# io-16x-fused-fm_v1_0_0.net
KiCad netlist of a schematic drawn in EAGLE
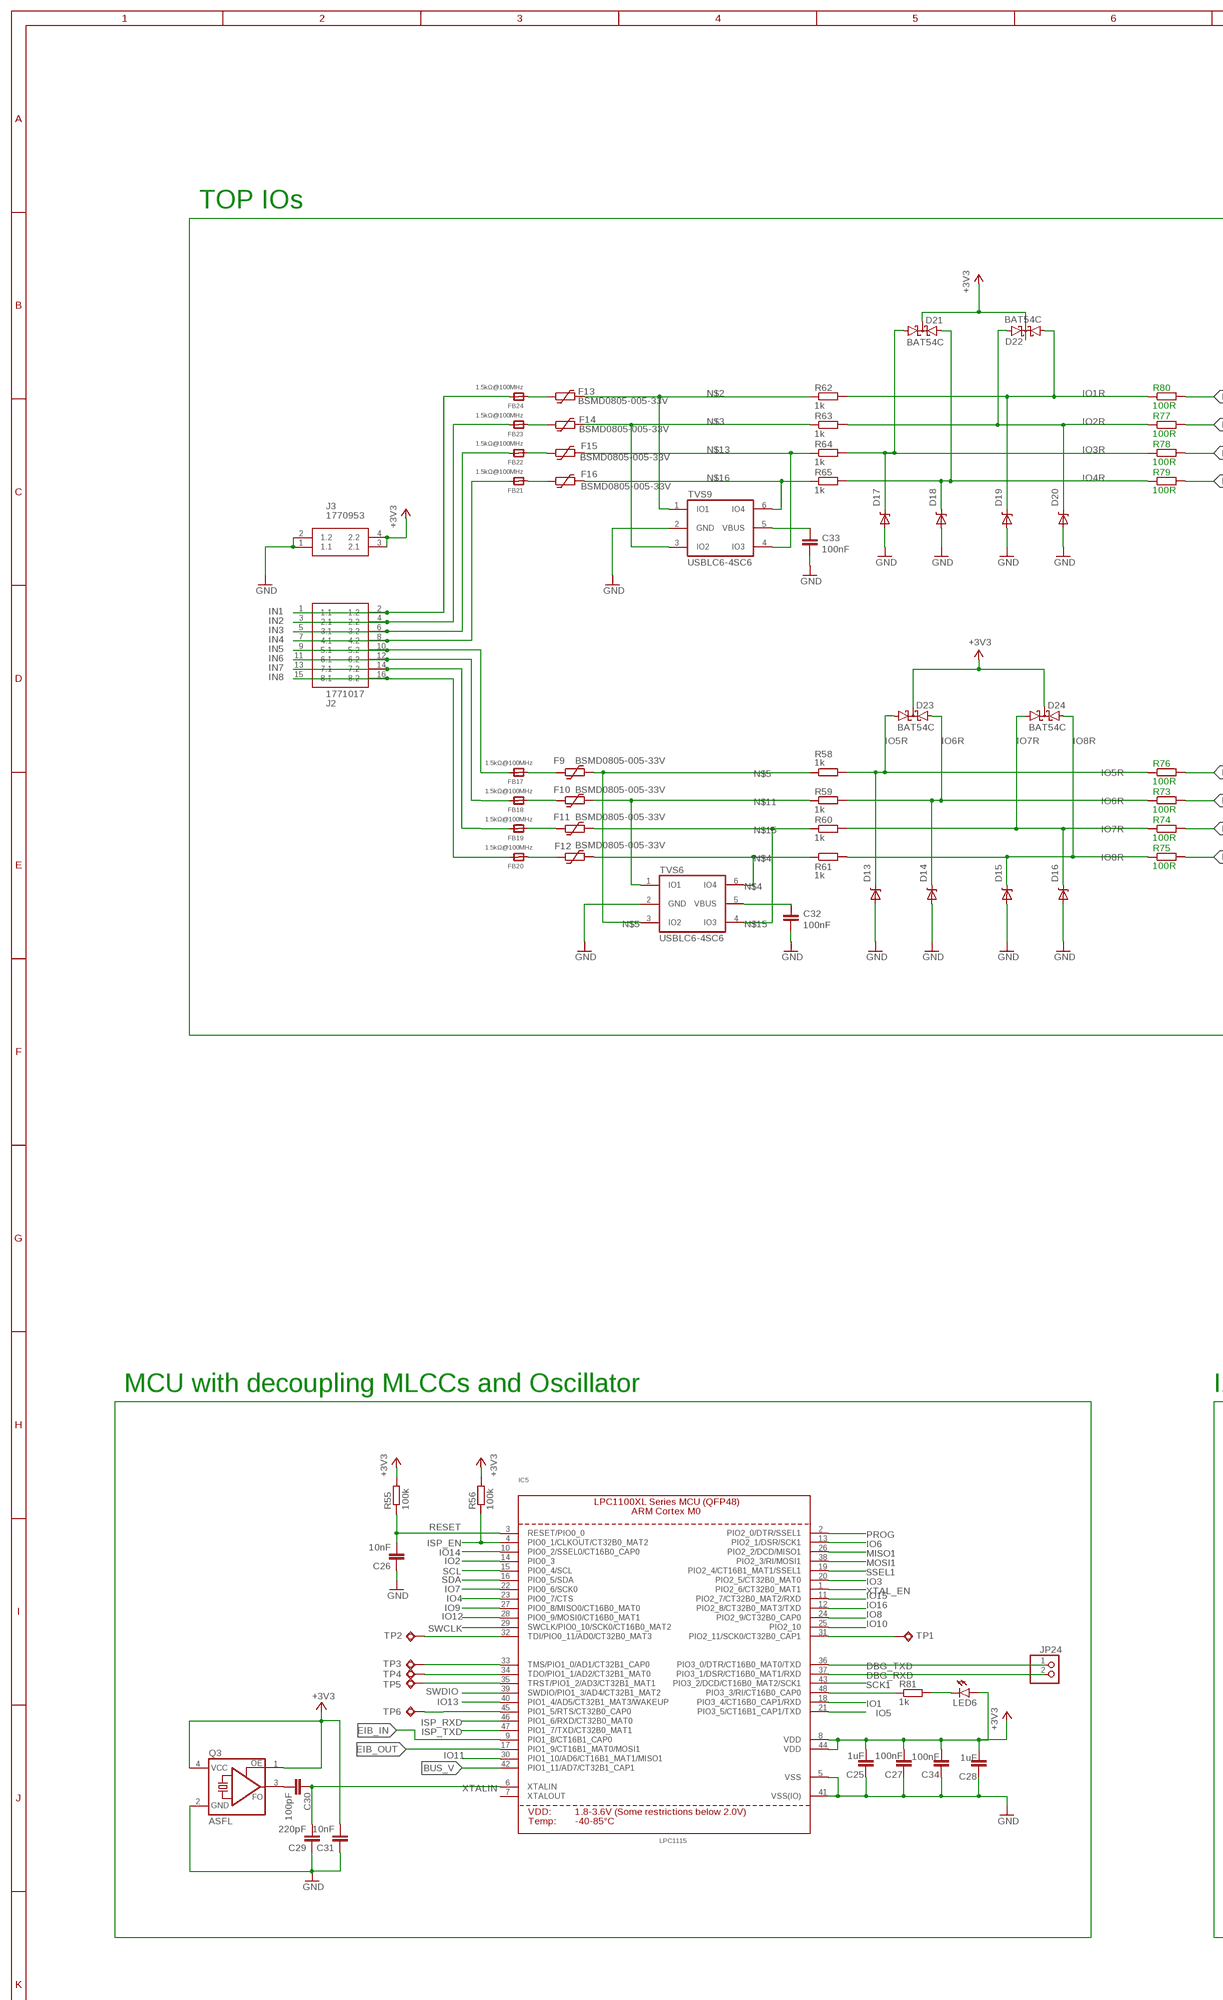
[diagram p0: schematic, sheet 1, part 1 of 3]
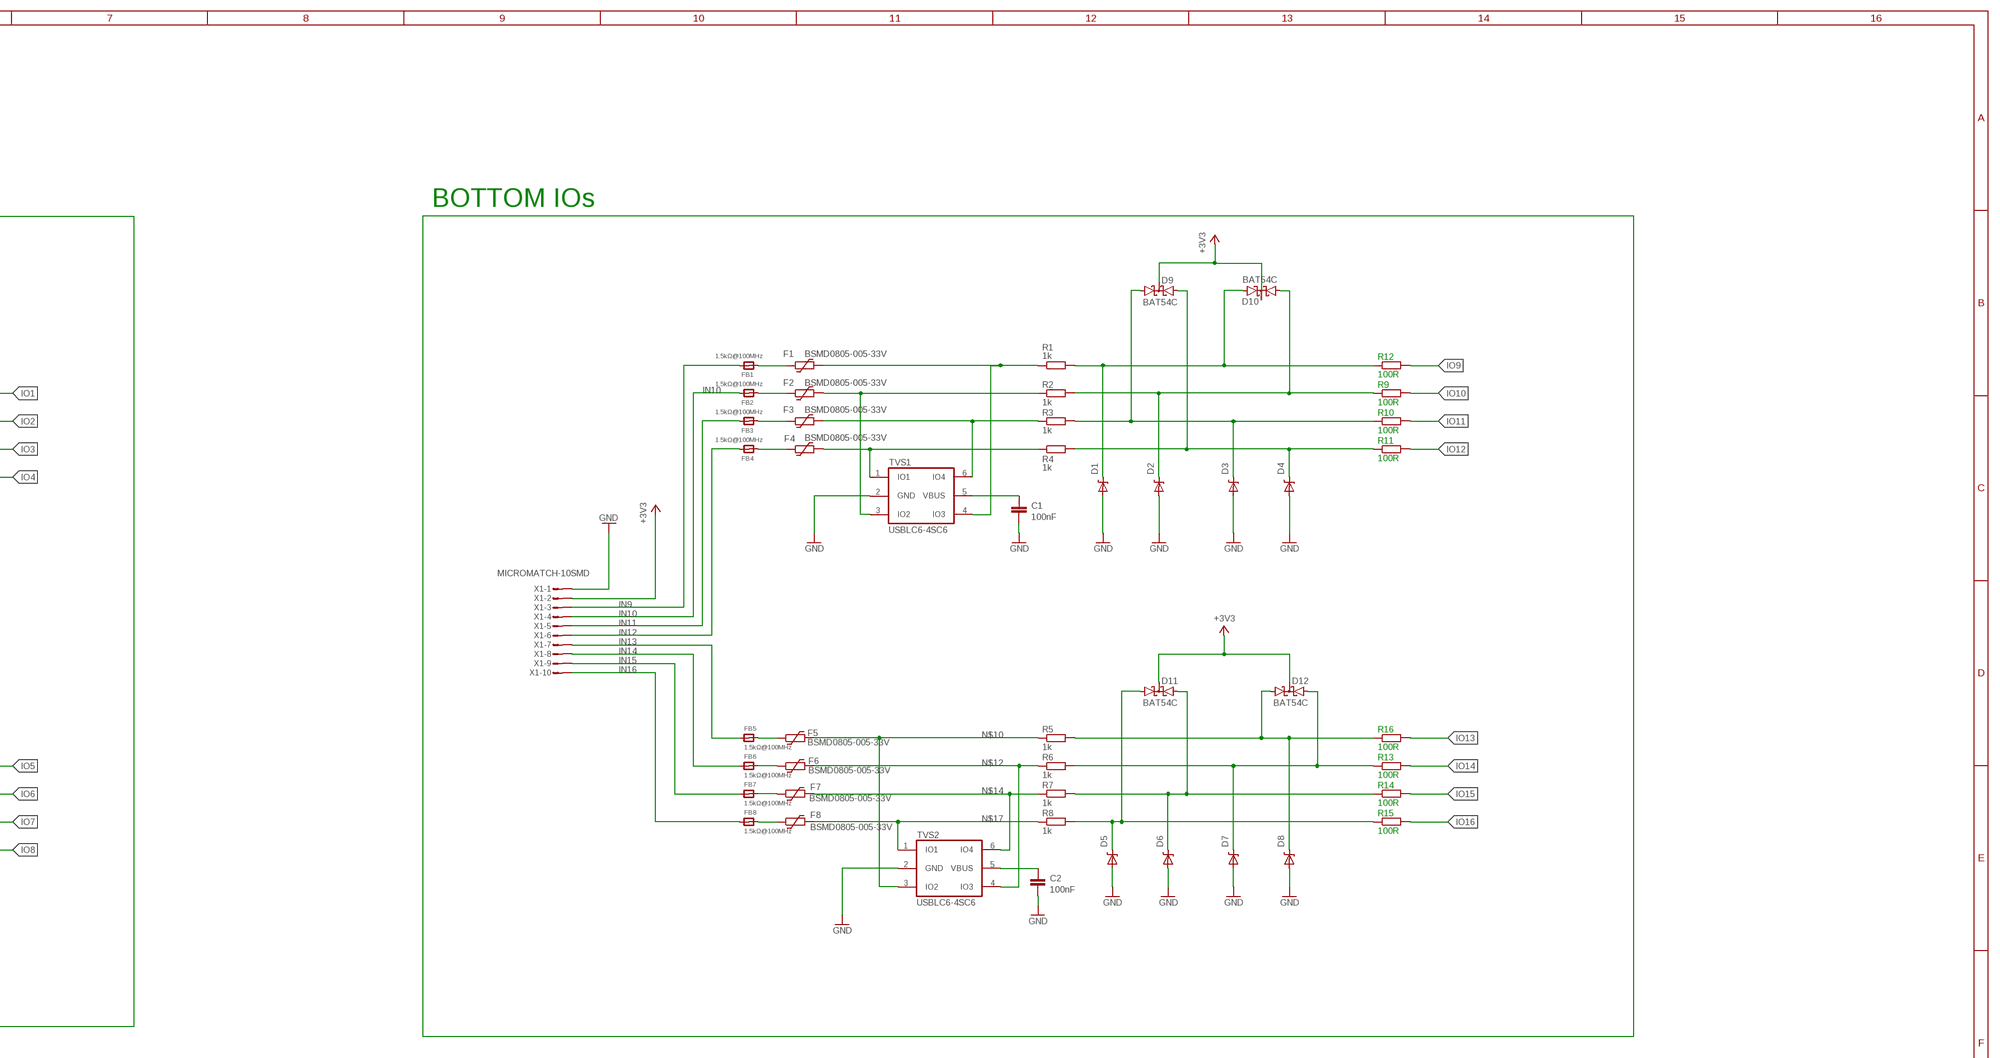
[diagram p1: schematic, sheet 1, part 2 of 3]
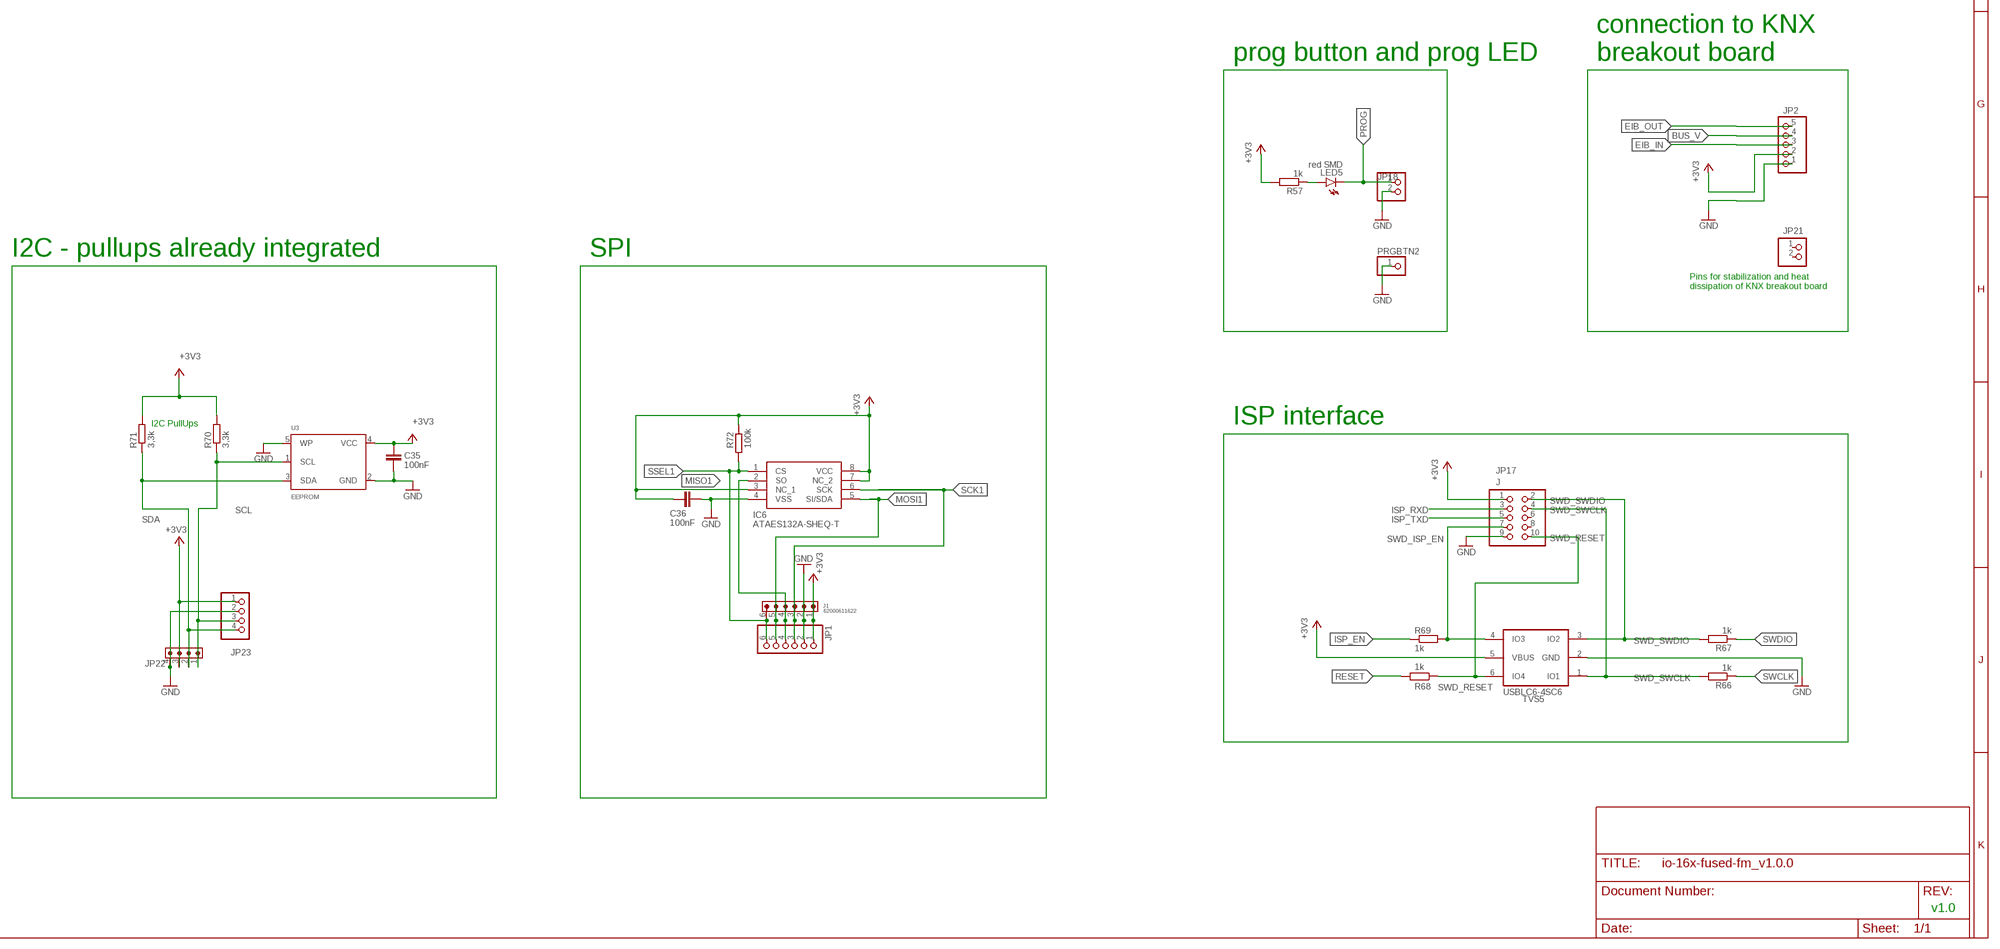
[diagram p2: schematic, sheet 1, part 3 of 3]

(export (version "E")
  (design (tool "Eeschema 10.0.6"))
  (components
    (comp (ref "C1")
      (value "100nF")
      (footprint "eagle-import:C0805")
      (libsource (lib "eagle-import") (part "C-EUC0805"))
    )
    (comp (ref "C2")
      (value "100nF")
      (footprint "eagle-import:C0805")
      (libsource (lib "eagle-import") (part "C-EUC0805"))
    )
    (comp (ref "C25")
      (value "1uF")
      (footprint "eagle-import:C0805")
      (libsource (lib "eagle-import") (part "C-EUC0805"))
    )
    (comp (ref "C26")
      (value "10nF")
      (footprint "eagle-import:C0805")
      (libsource (lib "eagle-import") (part "C-EUC0805"))
    )
    (comp (ref "C27")
      (value "100nF")
      (footprint "eagle-import:C0805")
      (libsource (lib "eagle-import") (part "C-EUC0805"))
    )
    (comp (ref "C28")
      (value "1uF")
      (footprint "eagle-import:C0805")
      (libsource (lib "eagle-import") (part "C-EUC0805"))
    )
    (comp (ref "C29")
      (value "220pF")
      (footprint "eagle-import:C0805")
      (libsource (lib "eagle-import") (part "C-EUC0805"))
    )
    (comp (ref "C30")
      (value "100pF")
      (footprint "eagle-import:C0805")
      (libsource (lib "eagle-import") (part "C-EUC0805"))
    )
    (comp (ref "C31")
      (value "10nF")
      (footprint "eagle-import:C0805")
      (libsource (lib "eagle-import") (part "C-EUC0805"))
    )
    (comp (ref "C32")
      (value "100nF")
      (footprint "eagle-import:C0805")
      (libsource (lib "eagle-import") (part "C-EUC0805"))
    )
    (comp (ref "C33")
      (value "100nF")
      (footprint "eagle-import:C0805")
      (libsource (lib "eagle-import") (part "C-EUC0805"))
    )
    (comp (ref "C34")
      (value "100nF")
      (footprint "eagle-import:C0805")
      (libsource (lib "eagle-import") (part "C-EUC0805"))
    )
    (comp (ref "C35")
      (value "100nF")
      (footprint "eagle-import:C0805")
      (libsource (lib "eagle-import") (part "C-EUC0805"))
    )
    (comp (ref "C36")
      (value "100nF")
      (footprint "eagle-import:C0805")
      (libsource (lib "eagle-import") (part "C-EUC0805"))
    )
    (comp (ref "D1")
      (value "DDZ9684")
      (footprint "eagle-import:SOD-123")
      (libsource (lib "eagle-import") (part "DIODE-ZENERSOD-123"))
    )
    (comp (ref "D2")
      (value "DDZ9684")
      (footprint "eagle-import:SOD-123")
      (libsource (lib "eagle-import") (part "DIODE-ZENERSOD-123"))
    )
    (comp (ref "D3")
      (value "DDZ9684")
      (footprint "eagle-import:SOD-123")
      (libsource (lib "eagle-import") (part "DIODE-ZENERSOD-123"))
    )
    (comp (ref "D4")
      (value "DDZ9684")
      (footprint "eagle-import:SOD-123")
      (libsource (lib "eagle-import") (part "DIODE-ZENERSOD-123"))
    )
    (comp (ref "D5")
      (value "DDZ9684")
      (footprint "eagle-import:SOD-123")
      (libsource (lib "eagle-import") (part "DIODE-ZENERSOD-123"))
    )
    (comp (ref "D6")
      (value "DDZ9684")
      (footprint "eagle-import:SOD-123")
      (libsource (lib "eagle-import") (part "DIODE-ZENERSOD-123"))
    )
    (comp (ref "D7")
      (value "DDZ9684")
      (footprint "eagle-import:SOD-123")
      (libsource (lib "eagle-import") (part "DIODE-ZENERSOD-123"))
    )
    (comp (ref "D8")
      (value "DDZ9684")
      (footprint "eagle-import:SOD-123")
      (libsource (lib "eagle-import") (part "DIODE-ZENERSOD-123"))
    )
    (comp (ref "D9")
      (value "BAT54C")
      (footprint "eagle-import:SOT23")
      (libsource (lib "eagle-import") (part "BAT54C"))
    )
    (comp (ref "D10")
      (value "BAT54C")
      (footprint "eagle-import:SOT23")
      (libsource (lib "eagle-import") (part "BAT54C"))
    )
    (comp (ref "D11")
      (value "BAT54C")
      (footprint "eagle-import:SOT23")
      (libsource (lib "eagle-import") (part "BAT54C"))
    )
    (comp (ref "D12")
      (value "BAT54C")
      (footprint "eagle-import:SOT23")
      (libsource (lib "eagle-import") (part "BAT54C"))
    )
    (comp (ref "D13")
      (value "DDZ9684")
      (footprint "eagle-import:SOD-123")
      (libsource (lib "eagle-import") (part "DIODE-ZENERSOD-123"))
    )
    (comp (ref "D14")
      (value "DDZ9684")
      (footprint "eagle-import:SOD-123")
      (libsource (lib "eagle-import") (part "DIODE-ZENERSOD-123"))
    )
    (comp (ref "D15")
      (value "DDZ9684")
      (footprint "eagle-import:SOD-123")
      (libsource (lib "eagle-import") (part "DIODE-ZENERSOD-123"))
    )
    (comp (ref "D16")
      (value "DDZ9684")
      (footprint "eagle-import:SOD-123")
      (libsource (lib "eagle-import") (part "DIODE-ZENERSOD-123"))
    )
    (comp (ref "D17")
      (value "DDZ9684")
      (footprint "eagle-import:SOD-123")
      (libsource (lib "eagle-import") (part "DIODE-ZENERSOD-123"))
    )
    (comp (ref "D18")
      (value "DDZ9684")
      (footprint "eagle-import:SOD-123")
      (libsource (lib "eagle-import") (part "DIODE-ZENERSOD-123"))
    )
    (comp (ref "D19")
      (value "DDZ9684")
      (footprint "eagle-import:SOD-123")
      (libsource (lib "eagle-import") (part "DIODE-ZENERSOD-123"))
    )
    (comp (ref "D20")
      (value "DDZ9684")
      (footprint "eagle-import:SOD-123")
      (libsource (lib "eagle-import") (part "DIODE-ZENERSOD-123"))
    )
    (comp (ref "D21")
      (value "BAT54C")
      (footprint "eagle-import:SOT23")
      (libsource (lib "eagle-import") (part "BAT54C"))
    )
    (comp (ref "D22")
      (value "BAT54C")
      (footprint "eagle-import:SOT23")
      (libsource (lib "eagle-import") (part "BAT54C"))
    )
    (comp (ref "D23")
      (value "BAT54C")
      (footprint "eagle-import:SOT23")
      (libsource (lib "eagle-import") (part "BAT54C"))
    )
    (comp (ref "D24")
      (value "BAT54C")
      (footprint "eagle-import:SOT23")
      (libsource (lib "eagle-import") (part "BAT54C"))
    )
    (comp (ref "F1")
      (value "BSMD0805-005-33V")
      (footprint "eagle-import:0805L")
      (fields (field (name "MF") "Littelfuse") (field (name "MPN") "0805L035"))
      (libsource (lib "eagle-import") (part "?0805L035"))
    )
    (comp (ref "F2")
      (value "BSMD0805-005-33V")
      (footprint "eagle-import:0805L")
      (fields (field (name "MF") "Littelfuse") (field (name "MPN") "0805L035"))
      (libsource (lib "eagle-import") (part "?0805L035"))
    )
    (comp (ref "F3")
      (value "BSMD0805-005-33V")
      (footprint "eagle-import:0805L")
      (fields (field (name "MF") "Littelfuse") (field (name "MPN") "0805L035"))
      (libsource (lib "eagle-import") (part "?0805L035"))
    )
    (comp (ref "F4")
      (value "BSMD0805-005-33V")
      (footprint "eagle-import:0805L")
      (fields (field (name "MF") "Littelfuse") (field (name "MPN") "0805L035"))
      (libsource (lib "eagle-import") (part "?0805L035"))
    )
    (comp (ref "F5")
      (value "BSMD0805-005-33V")
      (footprint "eagle-import:0805L")
      (fields (field (name "MF") "Littelfuse") (field (name "MPN") "0805L035"))
      (libsource (lib "eagle-import") (part "?0805L035"))
    )
    (comp (ref "F6")
      (value "BSMD0805-005-33V")
      (footprint "eagle-import:0805L")
      (fields (field (name "MF") "Littelfuse") (field (name "MPN") "0805L035"))
      (libsource (lib "eagle-import") (part "?0805L035"))
    )
    (comp (ref "F7")
      (value "BSMD0805-005-33V")
      (footprint "eagle-import:0805L")
      (fields (field (name "MF") "Littelfuse") (field (name "MPN") "0805L035"))
      (libsource (lib "eagle-import") (part "?0805L035"))
    )
    (comp (ref "F8")
      (value "BSMD0805-005-33V")
      (footprint "eagle-import:0805L")
      (fields (field (name "MF") "Littelfuse") (field (name "MPN") "0805L035"))
      (libsource (lib "eagle-import") (part "?0805L035"))
    )
    (comp (ref "F9")
      (value "BSMD0805-005-33V")
      (footprint "eagle-import:0805L")
      (fields (field (name "MF") "Littelfuse") (field (name "MPN") "0805L035"))
      (libsource (lib "eagle-import") (part "?0805L035"))
    )
    (comp (ref "F10")
      (value "BSMD0805-005-33V")
      (footprint "eagle-import:0805L")
      (fields (field (name "MF") "Littelfuse") (field (name "MPN") "0805L035"))
      (libsource (lib "eagle-import") (part "?0805L035"))
    )
    (comp (ref "F11")
      (value "BSMD0805-005-33V")
      (footprint "eagle-import:0805L")
      (fields (field (name "MF") "Littelfuse") (field (name "MPN") "0805L035"))
      (libsource (lib "eagle-import") (part "?0805L035"))
    )
    (comp (ref "F12")
      (value "BSMD0805-005-33V")
      (footprint "eagle-import:0805L")
      (fields (field (name "MF") "Littelfuse") (field (name "MPN") "0805L035"))
      (libsource (lib "eagle-import") (part "?0805L035"))
    )
    (comp (ref "F13")
      (value "BSMD0805-005-33V")
      (footprint "eagle-import:0805L")
      (fields (field (name "MF") "Littelfuse") (field (name "MPN") "0805L035"))
      (libsource (lib "eagle-import") (part "?0805L035"))
    )
    (comp (ref "F14")
      (value "BSMD0805-005-33V")
      (footprint "eagle-import:0805L")
      (fields (field (name "MF") "Littelfuse") (field (name "MPN") "0805L035"))
      (libsource (lib "eagle-import") (part "?0805L035"))
    )
    (comp (ref "F15")
      (value "BSMD0805-005-33V")
      (footprint "eagle-import:0805L")
      (fields (field (name "MF") "Littelfuse") (field (name "MPN") "0805L035"))
      (libsource (lib "eagle-import") (part "?0805L035"))
    )
    (comp (ref "F16")
      (value "BSMD0805-005-33V")
      (footprint "eagle-import:0805L")
      (fields (field (name "MF") "Littelfuse") (field (name "MPN") "0805L035"))
      (libsource (lib "eagle-import") (part "?0805L035"))
    )
    (comp (ref "FB1")
      (value "1.5kΩ@100MHz")
      (footprint "eagle-import:FERR_0805MP")
      (libsource (lib "eagle-import") (part "FERRITE2_0805MP"))
    )
    (comp (ref "FB2")
      (value "1.5kΩ@100MHz")
      (footprint "eagle-import:FERR_0805MP")
      (libsource (lib "eagle-import") (part "FERRITE2_0805MP"))
    )
    (comp (ref "FB3")
      (value "1.5kΩ@100MHz")
      (footprint "eagle-import:FERR_0805MP")
      (libsource (lib "eagle-import") (part "FERRITE2_0805MP"))
    )
    (comp (ref "FB4")
      (value "1.5kΩ@100MHz")
      (footprint "eagle-import:FERR_0805MP")
      (libsource (lib "eagle-import") (part "FERRITE2_0805MP"))
    )
    (comp (ref "FB5")
      (value "1.5kΩ@100MHz")
      (footprint "eagle-import:FERR_0805MP")
      (libsource (lib "eagle-import") (part "FERRITE2_0805MP"))
    )
    (comp (ref "FB6")
      (value "1.5kΩ@100MHz")
      (footprint "eagle-import:FERR_0805MP")
      (libsource (lib "eagle-import") (part "FERRITE2_0805MP"))
    )
    (comp (ref "FB7")
      (value "1.5kΩ@100MHz")
      (footprint "eagle-import:FERR_0805MP")
      (libsource (lib "eagle-import") (part "FERRITE2_0805MP"))
    )
    (comp (ref "FB8")
      (value "1.5kΩ@100MHz")
      (footprint "eagle-import:FERR_0805MP")
      (libsource (lib "eagle-import") (part "FERRITE2_0805MP"))
    )
    (comp (ref "FB17")
      (value "1.5kΩ@100MHz")
      (footprint "eagle-import:FERR_0805MP")
      (libsource (lib "eagle-import") (part "FERRITE2_0805MP"))
    )
    (comp (ref "FB18")
      (value "1.5kΩ@100MHz")
      (footprint "eagle-import:FERR_0805MP")
      (libsource (lib "eagle-import") (part "FERRITE2_0805MP"))
    )
    (comp (ref "FB19")
      (value "1.5kΩ@100MHz")
      (footprint "eagle-import:FERR_0805MP")
      (libsource (lib "eagle-import") (part "FERRITE2_0805MP"))
    )
    (comp (ref "FB20")
      (value "1.5kΩ@100MHz")
      (footprint "eagle-import:FERR_0805MP")
      (libsource (lib "eagle-import") (part "FERRITE2_0805MP"))
    )
    (comp (ref "FB21")
      (value "1.5kΩ@100MHz")
      (footprint "eagle-import:FERR_0805MP")
      (libsource (lib "eagle-import") (part "FERRITE2_0805MP"))
    )
    (comp (ref "FB22")
      (value "1.5kΩ@100MHz")
      (footprint "eagle-import:FERR_0805MP")
      (libsource (lib "eagle-import") (part "FERRITE2_0805MP"))
    )
    (comp (ref "FB23")
      (value "1.5kΩ@100MHz")
      (footprint "eagle-import:FERR_0805MP")
      (libsource (lib "eagle-import") (part "FERRITE2_0805MP"))
    )
    (comp (ref "FB24")
      (value "1.5kΩ@100MHz")
      (footprint "eagle-import:FERR_0805MP")
      (libsource (lib "eagle-import") (part "FERRITE2_0805MP"))
    )
    (comp (ref "IC5")
      (value "LPC1115")
      (footprint "eagle-import:LQFP48")
      (libsource (lib "eagle-import") (part "LPC1113/4/5_QFP48_XLSERIES"))
    )
    (comp (ref "IC6")
      (value "ATAES132A-SHEQ-T")
      (footprint "eagle-import:SOIC127P600X175-8N")
      (fields (field (name "MOUSER_PART_NUMBER") "556-ATAES132A-SHEQ-T"))
      (libsource (lib "eagle-import") (part "ATAES132A-SHEQ-T"))
    )
    (comp (ref "J1")
      (value "62000611622")
      (footprint "eagle-import:62000611622")
      (libsource (lib "eagle-import") (part "62000611622"))
    )
    (comp (ref "J2")
      (value "1771017")
      (footprint "eagle-import:1771017")
      (fields (field (name "MOUSER_PART_NUMBER") "651-1771017"))
      (libsource (lib "eagle-import") (part "1771017"))
    )
    (comp (ref "J3")
      (value "1770953")
      (footprint "eagle-import:1770953")
      (fields (field (name "MOUSER_PART_NUMBER") "651-1770953"))
      (libsource (lib "eagle-import") (part "1770953"))
    )
    (comp (ref "JP1")
      (value "PINHD-1X06_2.54-S")
      (footprint "eagle-import:1X06-S")
      (libsource (lib "eagle-import") (part "PINHD-1X06_2.54-S"))
    )
    (comp (ref "JP2")
      (value "PINHD-1X5")
      (footprint "eagle-import:1X05")
      (libsource (lib "eagle-import") (part "PINHD-1X5"))
    )
    (comp (ref "JP17")
      (value "J")
      (footprint "eagle-import:2X05M")
      (libsource (lib "eagle-import") (part "PINHD-2X05_2.00"))
    )
    (comp (ref "JP18")
      (value "PINHD-1X2")
      (footprint "eagle-import:1X02")
      (libsource (lib "eagle-import") (part "PINHD-1X2"))
    )
    (comp (ref "JP21")
      (value "PINHD-1X2")
      (footprint "eagle-import:1X02")
      (libsource (lib "eagle-import") (part "PINHD-1X2"))
    )
    (comp (ref "JP22")
      (value "62000411622")
      (footprint "eagle-import:62000411622")
      (libsource (lib "eagle-import") (part "62000411622"))
    )
    (comp (ref "JP23")
      (value "PINHD-1X4")
      (footprint "eagle-import:1X04")
      (libsource (lib "eagle-import") (part "PINHD-1X4"))
    )
    (comp (ref "JP24")
      (value "PINHD-1X2")
      (footprint "eagle-import:1X02")
      (libsource (lib "eagle-import") (part "PINHD-1X2"))
    )
    (comp (ref "LED5")
      (value "red SMD")
      (footprint "eagle-import:CHIPLED_0805")
      (libsource (lib "eagle-import") (part "LEDCHIPLED_0805"))
    )
    (comp (ref "LED6")
      (value "LEDCHIPLED_0805")
      (footprint "eagle-import:CHIPLED_0805")
      (libsource (lib "eagle-import") (part "LEDCHIPLED_0805"))
    )
    (comp (ref "PRGBTN2")
      (value "PINHD-1X1")
      (footprint "eagle-import:1X01")
      (libsource (lib "eagle-import") (part "PINHD-1X1"))
    )
    (comp (ref "Q3")
      (value "ASFL")
      (footprint "eagle-import:ASF")
      (fields (field (name "MPN") "ASFLM1-50.000MHZ-C-T"))
      (libsource (lib "eagle-import") (part "ASFL"))
    )
    (comp (ref "R1")
      (value "1k")
      (footprint "eagle-import:R0805")
      (libsource (lib "eagle-import") (part "R-EU_R0805"))
    )
    (comp (ref "R2")
      (value "1k")
      (footprint "eagle-import:R0805")
      (libsource (lib "eagle-import") (part "R-EU_R0805"))
    )
    (comp (ref "R3")
      (value "1k")
      (footprint "eagle-import:R0805")
      (libsource (lib "eagle-import") (part "R-EU_R0805"))
    )
    (comp (ref "R4")
      (value "1k")
      (footprint "eagle-import:R0805")
      (libsource (lib "eagle-import") (part "R-EU_R0805"))
    )
    (comp (ref "R5")
      (value "1k")
      (footprint "eagle-import:R0805")
      (libsource (lib "eagle-import") (part "R-EU_R0805"))
    )
    (comp (ref "R6")
      (value "1k")
      (footprint "eagle-import:R0805")
      (libsource (lib "eagle-import") (part "R-EU_R0805"))
    )
    (comp (ref "R7")
      (value "1k")
      (footprint "eagle-import:R0805")
      (libsource (lib "eagle-import") (part "R-EU_R0805"))
    )
    (comp (ref "R8")
      (value "1k")
      (footprint "eagle-import:R0805")
      (libsource (lib "eagle-import") (part "R-EU_R0805"))
    )
    (comp (ref "R9")
      (value "100R")
      (footprint "eagle-import:R0805")
      (libsource (lib "eagle-import") (part "R-EU_R0805"))
    )
    (comp (ref "R10")
      (value "100R")
      (footprint "eagle-import:R0805")
      (libsource (lib "eagle-import") (part "R-EU_R0805"))
    )
    (comp (ref "R11")
      (value "100R")
      (footprint "eagle-import:R0805")
      (libsource (lib "eagle-import") (part "R-EU_R0805"))
    )
    (comp (ref "R12")
      (value "100R")
      (footprint "eagle-import:R0805")
      (libsource (lib "eagle-import") (part "R-EU_R0805"))
    )
    (comp (ref "R13")
      (value "100R")
      (footprint "eagle-import:R0805")
      (libsource (lib "eagle-import") (part "R-EU_R0805"))
    )
    (comp (ref "R14")
      (value "100R")
      (footprint "eagle-import:R0805")
      (libsource (lib "eagle-import") (part "R-EU_R0805"))
    )
    (comp (ref "R15")
      (value "100R")
      (footprint "eagle-import:R0805")
      (libsource (lib "eagle-import") (part "R-EU_R0805"))
    )
    (comp (ref "R16")
      (value "100R")
      (footprint "eagle-import:R0805")
      (libsource (lib "eagle-import") (part "R-EU_R0805"))
    )
    (comp (ref "R55")
      (value "100k")
      (footprint "eagle-import:R0805")
      (libsource (lib "eagle-import") (part "R-EU_R0805"))
    )
    (comp (ref "R56")
      (value "100k")
      (footprint "eagle-import:R0805")
      (libsource (lib "eagle-import") (part "R-EU_R0805"))
    )
    (comp (ref "R57")
      (value "1k")
      (footprint "eagle-import:R0805")
      (libsource (lib "eagle-import") (part "R-EU_R0805"))
    )
    (comp (ref "R58")
      (value "1k")
      (footprint "eagle-import:R0805")
      (libsource (lib "eagle-import") (part "R-EU_R0805"))
    )
    (comp (ref "R59")
      (value "1k")
      (footprint "eagle-import:R0805")
      (libsource (lib "eagle-import") (part "R-EU_R0805"))
    )
    (comp (ref "R60")
      (value "1k")
      (footprint "eagle-import:R0805")
      (libsource (lib "eagle-import") (part "R-EU_R0805"))
    )
    (comp (ref "R61")
      (value "1k")
      (footprint "eagle-import:R0805")
      (libsource (lib "eagle-import") (part "R-EU_R0805"))
    )
    (comp (ref "R62")
      (value "1k")
      (footprint "eagle-import:R0805")
      (libsource (lib "eagle-import") (part "R-EU_R0805"))
    )
    (comp (ref "R63")
      (value "1k")
      (footprint "eagle-import:R0805")
      (libsource (lib "eagle-import") (part "R-EU_R0805"))
    )
    (comp (ref "R64")
      (value "1k")
      (footprint "eagle-import:R0805")
      (libsource (lib "eagle-import") (part "R-EU_R0805"))
    )
    (comp (ref "R65")
      (value "1k")
      (footprint "eagle-import:R0805")
      (libsource (lib "eagle-import") (part "R-EU_R0805"))
    )
    (comp (ref "R66")
      (value "1k")
      (footprint "eagle-import:R0805")
      (libsource (lib "eagle-import") (part "R-EU_R0805"))
    )
    (comp (ref "R67")
      (value "1k")
      (footprint "eagle-import:R0805")
      (libsource (lib "eagle-import") (part "R-EU_R0805"))
    )
    (comp (ref "R68")
      (value "1k")
      (footprint "eagle-import:R0805")
      (libsource (lib "eagle-import") (part "R-EU_R0805"))
    )
    (comp (ref "R69")
      (value "1k")
      (footprint "eagle-import:R0805")
      (libsource (lib "eagle-import") (part "R-EU_R0805"))
    )
    (comp (ref "R70")
      (value "3,3k")
      (footprint "eagle-import:R0805")
      (libsource (lib "eagle-import") (part "R-EU_R0805"))
    )
    (comp (ref "R71")
      (value "3,3k")
      (footprint "eagle-import:R0805")
      (libsource (lib "eagle-import") (part "R-EU_R0805"))
    )
    (comp (ref "R72")
      (value "100k")
      (footprint "eagle-import:R0805")
      (libsource (lib "eagle-import") (part "R-EU_R0805"))
    )
    (comp (ref "R73")
      (value "100R")
      (footprint "eagle-import:R0805")
      (libsource (lib "eagle-import") (part "R-EU_R0805"))
    )
    (comp (ref "R74")
      (value "100R")
      (footprint "eagle-import:R0805")
      (libsource (lib "eagle-import") (part "R-EU_R0805"))
    )
    (comp (ref "R75")
      (value "100R")
      (footprint "eagle-import:R0805")
      (libsource (lib "eagle-import") (part "R-EU_R0805"))
    )
    (comp (ref "R76")
      (value "100R")
      (footprint "eagle-import:R0805")
      (libsource (lib "eagle-import") (part "R-EU_R0805"))
    )
    (comp (ref "R77")
      (value "100R")
      (footprint "eagle-import:R0805")
      (libsource (lib "eagle-import") (part "R-EU_R0805"))
    )
    (comp (ref "R78")
      (value "100R")
      (footprint "eagle-import:R0805")
      (libsource (lib "eagle-import") (part "R-EU_R0805"))
    )
    (comp (ref "R79")
      (value "100R")
      (footprint "eagle-import:R0805")
      (libsource (lib "eagle-import") (part "R-EU_R0805"))
    )
    (comp (ref "R80")
      (value "100R")
      (footprint "eagle-import:R0805")
      (libsource (lib "eagle-import") (part "R-EU_R0805"))
    )
    (comp (ref "R81")
      (value "1k")
      (footprint "eagle-import:R0805")
      (libsource (lib "eagle-import") (part "R-EU_R0805"))
    )
    (comp (ref "TP1")
      (value "TPSQTP08R")
      (footprint "eagle-import:TP08R")
      (libsource (lib "eagle-import") (part "TPSQTP08R"))
    )
    (comp (ref "TP2")
      (value "TPSQTP08R")
      (footprint "eagle-import:TP08R")
      (libsource (lib "eagle-import") (part "TPSQTP08R"))
    )
    (comp (ref "TP3")
      (value "TPSQTP08R")
      (footprint "eagle-import:TP08R")
      (libsource (lib "eagle-import") (part "TPSQTP08R"))
    )
    (comp (ref "TP4")
      (value "TPSQTP08R")
      (footprint "eagle-import:TP08R")
      (libsource (lib "eagle-import") (part "TPSQTP08R"))
    )
    (comp (ref "TP5")
      (value "TPSQTP08R")
      (footprint "eagle-import:TP08R")
      (libsource (lib "eagle-import") (part "TPSQTP08R"))
    )
    (comp (ref "TP6")
      (value "TPSQTP08R")
      (footprint "eagle-import:TP08R")
      (libsource (lib "eagle-import") (part "TPSQTP08R"))
    )
    (comp (ref "TVS1")
      (value "USBLC6-4SC6")
      (footprint "eagle-import:SOT-23-6L")
      (libsource (lib "eagle-import") (part "USBLC6-4SC6"))
    )
    (comp (ref "TVS2")
      (value "USBLC6-4SC6")
      (footprint "eagle-import:SOT-23-6L")
      (libsource (lib "eagle-import") (part "USBLC6-4SC6"))
    )
    (comp (ref "TVS5")
      (value "USBLC6-4SC6")
      (footprint "eagle-import:SOT-23-6L")
      (libsource (lib "eagle-import") (part "USBLC6-4SC6"))
    )
    (comp (ref "TVS6")
      (value "USBLC6-4SC6")
      (footprint "eagle-import:SOT-23-6L")
      (libsource (lib "eagle-import") (part "USBLC6-4SC6"))
    )
    (comp (ref "TVS9")
      (value "USBLC6-4SC6")
      (footprint "eagle-import:SOT-23-6L")
      (libsource (lib "eagle-import") (part "USBLC6-4SC6"))
    )
    (comp (ref "U3")
      (value "EEPROM")
      (footprint "eagle-import:SOT23-5")
      (libsource (lib "eagle-import") (part "EEPROM_I2C_MCP24AA32"))
    )
    (comp (ref "X1")
      (value "MICROMATCH-10SMD")
      (footprint "eagle-import:MICROMATCH-10SMD")
      (libsource (lib "eagle-import") (part "MICROMATCH-10SMD"))
    )
  )
  (nets
    (net (code "1") (name "+3V3") (class "Default")
      (node (ref "C25") (pin "2") (pinfunction "2_2") (pintype "passive"))
      (node (ref "C27") (pin "2") (pinfunction "2_2") (pintype "passive"))
      (node (ref "C28") (pin "2") (pinfunction "2_2") (pintype "passive"))
      (node (ref "C31") (pin "2") (pinfunction "2_2") (pintype "passive"))
      (node (ref "C34") (pin "2") (pinfunction "2_2") (pintype "passive"))
      (node (ref "C35") (pin "1") (pinfunction "1_1") (pintype "passive"))
      (node (ref "C36") (pin "1") (pinfunction "1_1") (pintype "passive"))
      (node (ref "D10") (pin "3") (pinfunction "CC_3") (pintype "passive"))
      (node (ref "D11") (pin "3") (pinfunction "CC_3") (pintype "passive"))
      (node (ref "D12") (pin "3") (pinfunction "CC_3") (pintype "passive"))
      (node (ref "D21") (pin "3") (pinfunction "CC_3") (pintype "passive"))
      (node (ref "D22") (pin "3") (pinfunction "CC_3") (pintype "passive"))
      (node (ref "D23") (pin "3") (pinfunction "CC_3") (pintype "passive"))
      (node (ref "D24") (pin "3") (pinfunction "CC_3") (pintype "passive"))
      (node (ref "D9") (pin "3") (pinfunction "CC_3") (pintype "passive"))
      (node (ref "IC5") (pin "44") (pinfunction "VDD_44") (pintype "power_in"))
      (node (ref "IC5") (pin "8") (pinfunction "VDD_8") (pintype "power_in"))
      (node (ref "IC6") (pin "3") (pinfunction "NC_1_3") (pintype "bidirectional"))
      (node (ref "IC6") (pin "7") (pinfunction "NC_2_7") (pintype "bidirectional"))
      (node (ref "IC6") (pin "8") (pinfunction "VCC_8") (pintype "bidirectional"))
      (node (ref "J1") (pin "1") (pinfunction "1_1") (pintype "passive"))
      (node (ref "J3") (pin "3") (pinfunction "2.1_3") (pintype "bidirectional"))
      (node (ref "J3") (pin "4") (pinfunction "2.2_4") (pintype "bidirectional"))
      (node (ref "JP1") (pin "1") (pinfunction "1_1") (pintype "passive"))
      (node (ref "JP17") (pin "1") (pinfunction "1_1") (pintype "passive"))
      (node (ref "JP2") (pin "2") (pinfunction "2_2") (pintype "passive"))
      (node (ref "JP22") (pin "3") (pinfunction "3_3") (pintype "passive"))
      (node (ref "JP23") (pin "1") (pinfunction "1_1") (pintype "passive"))
      (node (ref "LED6") (pin "A") (pinfunction "A_A") (pintype "passive"))
      (node (ref "Q3") (pin "1") (pinfunction "OE_1") (pintype "input"))
      (node (ref "Q3") (pin "4") (pinfunction "VCC_4") (pintype "power_in"))
      (node (ref "R55") (pin "2") (pinfunction "2_2") (pintype "passive"))
      (node (ref "R56") (pin "2") (pinfunction "2_2") (pintype "passive"))
      (node (ref "R57") (pin "2") (pinfunction "2_2") (pintype "passive"))
      (node (ref "R70") (pin "2") (pinfunction "2_2") (pintype "passive"))
      (node (ref "R71") (pin "2") (pinfunction "2_2") (pintype "passive"))
      (node (ref "R72") (pin "2") (pinfunction "2_2") (pintype "passive"))
      (node (ref "TVS5") (pin "5") (pinfunction "VBUS_5") (pintype "bidirectional"))
      (node (ref "U3") (pin "4") (pinfunction "VCC_4") (pintype "bidirectional"))
      (node (ref "X1") (pin "2") (pinfunction "S_2") (pintype "passive"))
    )
    (net (code "2") (name "/DBG_RXD") (class "Default")
      (node (ref "IC5") (pin "37") (pinfunction "PIO3_1/DSR/CT16B0_MAT1/RXD_37") (pintype "bidirectional"))
      (node (ref "JP24") (pin "2") (pinfunction "2_2") (pintype "passive"))
    )
    (net (code "3") (name "/DBG_TXD") (class "Default")
      (node (ref "IC5") (pin "36") (pinfunction "PIO3_0/DTR/CT16B0_MAT0/TXD_36") (pintype "bidirectional"))
      (node (ref "JP24") (pin "1") (pinfunction "1_1") (pintype "passive"))
    )
    (net (code "4") (name "/IN1") (class "Default")
      (node (ref "FB24") (pin "2") (pinfunction "P$2_2") (pintype "passive"))
      (node (ref "J2") (pin "1") (pinfunction "1.1_1") (pintype "bidirectional"))
      (node (ref "J2") (pin "2") (pinfunction "1.2_2") (pintype "bidirectional"))
    )
    (net (code "5") (name "/IN2") (class "Default")
      (node (ref "FB23") (pin "2") (pinfunction "P$2_2") (pintype "passive"))
      (node (ref "J2") (pin "3") (pinfunction "2.1_3") (pintype "bidirectional"))
      (node (ref "J2") (pin "4") (pinfunction "2.2_4") (pintype "bidirectional"))
    )
    (net (code "6") (name "/IN3") (class "Default")
      (node (ref "FB22") (pin "2") (pinfunction "P$2_2") (pintype "passive"))
      (node (ref "J2") (pin "5") (pinfunction "3.1_5") (pintype "bidirectional"))
      (node (ref "J2") (pin "6") (pinfunction "3.2_6") (pintype "bidirectional"))
    )
    (net (code "7") (name "/IN4") (class "Default")
      (node (ref "FB21") (pin "2") (pinfunction "P$2_2") (pintype "passive"))
      (node (ref "J2") (pin "7") (pinfunction "4.1_7") (pintype "bidirectional"))
      (node (ref "J2") (pin "8") (pinfunction "4.2_8") (pintype "bidirectional"))
    )
    (net (code "8") (name "/IN5") (class "Default")
      (node (ref "FB17") (pin "2") (pinfunction "P$2_2") (pintype "passive"))
      (node (ref "J2") (pin "10") (pinfunction "5.2_10") (pintype "bidirectional"))
      (node (ref "J2") (pin "9") (pinfunction "5.1_9") (pintype "bidirectional"))
    )
    (net (code "9") (name "/IN6") (class "Default")
      (node (ref "FB18") (pin "2") (pinfunction "P$2_2") (pintype "passive"))
      (node (ref "J2") (pin "11") (pinfunction "6.1_11") (pintype "bidirectional"))
      (node (ref "J2") (pin "12") (pinfunction "6.2_12") (pintype "bidirectional"))
    )
    (net (code "10") (name "/IN7") (class "Default")
      (node (ref "FB19") (pin "2") (pinfunction "P$2_2") (pintype "passive"))
      (node (ref "J2") (pin "13") (pinfunction "7.1_13") (pintype "bidirectional"))
      (node (ref "J2") (pin "14") (pinfunction "7.2_14") (pintype "bidirectional"))
    )
    (net (code "11") (name "/IN8") (class "Default")
      (node (ref "FB20") (pin "2") (pinfunction "P$2_2") (pintype "passive"))
      (node (ref "J2") (pin "15") (pinfunction "8.1_15") (pintype "bidirectional"))
      (node (ref "J2") (pin "16") (pinfunction "8.2_16") (pintype "bidirectional"))
    )
    (net (code "12") (name "/IN9") (class "Default")
      (node (ref "FB1") (pin "2") (pinfunction "P$2_2") (pintype "passive"))
      (node (ref "X1") (pin "3") (pinfunction "S_3") (pintype "passive"))
    )
    (net (code "13") (name "/IN10") (class "Default")
      (node (ref "FB2") (pin "2") (pinfunction "P$2_2") (pintype "passive"))
      (node (ref "X1") (pin "4") (pinfunction "S_4") (pintype "passive"))
    )
    (net (code "14") (name "/IN11") (class "Default")
      (node (ref "FB3") (pin "2") (pinfunction "P$2_2") (pintype "passive"))
      (node (ref "X1") (pin "5") (pinfunction "S_5") (pintype "passive"))
    )
    (net (code "15") (name "/IN12") (class "Default")
      (node (ref "FB4") (pin "2") (pinfunction "P$2_2") (pintype "passive"))
      (node (ref "X1") (pin "6") (pinfunction "S_6") (pintype "passive"))
    )
    (net (code "16") (name "/IN13") (class "Default")
      (node (ref "FB5") (pin "1") (pinfunction "P$1_1") (pintype "passive"))
      (node (ref "X1") (pin "7") (pinfunction "S_7") (pintype "passive"))
    )
    (net (code "17") (name "/IN14") (class "Default")
      (node (ref "FB6") (pin "1") (pinfunction "P$1_1") (pintype "passive"))
      (node (ref "X1") (pin "8") (pinfunction "S_8") (pintype "passive"))
    )
    (net (code "18") (name "/IN15") (class "Default")
      (node (ref "FB7") (pin "1") (pinfunction "P$1_1") (pintype "passive"))
      (node (ref "X1") (pin "9") (pinfunction "S_9") (pintype "passive"))
    )
    (net (code "19") (name "/IN16") (class "Default")
      (node (ref "FB8") (pin "1") (pinfunction "P$1_1") (pintype "passive"))
      (node (ref "X1") (pin "10") (pinfunction "S_10") (pintype "passive"))
    )
    (net (code "20") (name "/IO1R") (class "Default")
      (node (ref "D19") (pin "C") (pinfunction "C_C") (pintype "passive"))
      (node (ref "D22") (pin "1") (pinfunction "A1_1") (pintype "passive"))
      (node (ref "R62") (pin "2") (pinfunction "2_2") (pintype "passive"))
      (node (ref "R80") (pin "1") (pinfunction "1_1") (pintype "passive"))
    )
    (net (code "21") (name "/IO2R") (class "Default")
      (node (ref "D20") (pin "C") (pinfunction "C_C") (pintype "passive"))
      (node (ref "D22") (pin "2") (pinfunction "A2_2") (pintype "passive"))
      (node (ref "R63") (pin "2") (pinfunction "2_2") (pintype "passive"))
      (node (ref "R77") (pin "1") (pinfunction "1_1") (pintype "passive"))
    )
    (net (code "22") (name "/IO3R") (class "Default")
      (node (ref "D17") (pin "C") (pinfunction "C_C") (pintype "passive"))
      (node (ref "D21") (pin "1") (pinfunction "A1_1") (pintype "passive"))
      (node (ref "R64") (pin "2") (pinfunction "2_2") (pintype "passive"))
      (node (ref "R78") (pin "1") (pinfunction "1_1") (pintype "passive"))
    )
    (net (code "23") (name "/IO4R") (class "Default")
      (node (ref "D18") (pin "C") (pinfunction "C_C") (pintype "passive"))
      (node (ref "D21") (pin "2") (pinfunction "A2_2") (pintype "passive"))
      (node (ref "R65") (pin "2") (pinfunction "2_2") (pintype "passive"))
      (node (ref "R79") (pin "1") (pinfunction "1_1") (pintype "passive"))
    )
    (net (code "24") (name "/IO5R") (class "Default")
      (node (ref "D13") (pin "C") (pinfunction "C_C") (pintype "passive"))
      (node (ref "D23") (pin "1") (pinfunction "A1_1") (pintype "passive"))
      (node (ref "R58") (pin "2") (pinfunction "2_2") (pintype "passive"))
      (node (ref "R76") (pin "1") (pinfunction "1_1") (pintype "passive"))
    )
    (net (code "25") (name "/IO6R") (class "Default")
      (node (ref "D14") (pin "C") (pinfunction "C_C") (pintype "passive"))
      (node (ref "D23") (pin "2") (pinfunction "A2_2") (pintype "passive"))
      (node (ref "R59") (pin "2") (pinfunction "2_2") (pintype "passive"))
      (node (ref "R73") (pin "1") (pinfunction "1_1") (pintype "passive"))
    )
    (net (code "26") (name "/IO7R") (class "Default")
      (node (ref "D16") (pin "C") (pinfunction "C_C") (pintype "passive"))
      (node (ref "D24") (pin "1") (pinfunction "A1_1") (pintype "passive"))
      (node (ref "R60") (pin "2") (pinfunction "2_2") (pintype "passive"))
      (node (ref "R74") (pin "1") (pinfunction "1_1") (pintype "passive"))
    )
    (net (code "27") (name "/IO8R") (class "Default")
      (node (ref "D15") (pin "C") (pinfunction "C_C") (pintype "passive"))
      (node (ref "D24") (pin "2") (pinfunction "A2_2") (pintype "passive"))
      (node (ref "R61") (pin "2") (pinfunction "2_2") (pintype "passive"))
      (node (ref "R75") (pin "1") (pinfunction "1_1") (pintype "passive"))
    )
    (net (code "28") (name "/ISP_RXD") (class "Default")
      (node (ref "IC5") (pin "46") (pinfunction "PIO1_6/RXD/CT32B0_MAT0_46") (pintype "bidirectional"))
      (node (ref "JP17") (pin "3") (pinfunction "3_3") (pintype "passive"))
    )
    (net (code "29") (name "/ISP_TXD") (class "Default")
      (node (ref "IC5") (pin "47") (pinfunction "PIO1_7/TXD/CT32B0_MAT1_47") (pintype "bidirectional"))
      (node (ref "JP17") (pin "5") (pinfunction "5_5") (pintype "passive"))
    )
    (net (code "30") (name "/N$2") (class "Default")
      (node (ref "F13") (pin "2") (pinfunction "2_2") (pintype "passive"))
      (node (ref "R62") (pin "1") (pinfunction "1_1") (pintype "passive"))
      (node (ref "TVS9") (pin "1") (pinfunction "IO1_1") (pintype "bidirectional"))
    )
    (net (code "31") (name "/N$3") (class "Default")
      (node (ref "F14") (pin "2") (pinfunction "2_2") (pintype "passive"))
      (node (ref "R63") (pin "1") (pinfunction "1_1") (pintype "passive"))
      (node (ref "TVS9") (pin "3") (pinfunction "IO2_3") (pintype "bidirectional"))
    )
    (net (code "32") (name "/N$4") (class "Default")
      (node (ref "F12") (pin "2") (pinfunction "2_2") (pintype "passive"))
      (node (ref "R61") (pin "1") (pinfunction "1_1") (pintype "passive"))
      (node (ref "TVS6") (pin "6") (pinfunction "IO4_6") (pintype "bidirectional"))
    )
    (net (code "33") (name "/N$5") (class "Default")
      (node (ref "F9") (pin "2") (pinfunction "2_2") (pintype "passive"))
      (node (ref "R58") (pin "1") (pinfunction "1_1") (pintype "passive"))
      (node (ref "TVS6") (pin "3") (pinfunction "IO2_3") (pintype "bidirectional"))
    )
    (net (code "34") (name "/N$10") (class "Default")
      (node (ref "F5") (pin "2") (pinfunction "2_2") (pintype "passive"))
      (node (ref "R5") (pin "1") (pinfunction "1_1") (pintype "passive"))
      (node (ref "TVS2") (pin "3") (pinfunction "IO2_3") (pintype "bidirectional"))
    )
    (net (code "35") (name "/N$11") (class "Default")
      (node (ref "F10") (pin "2") (pinfunction "2_2") (pintype "passive"))
      (node (ref "R59") (pin "1") (pinfunction "1_1") (pintype "passive"))
      (node (ref "TVS6") (pin "1") (pinfunction "IO1_1") (pintype "bidirectional"))
    )
    (net (code "36") (name "/N$12") (class "Default")
      (node (ref "F6") (pin "2") (pinfunction "2_2") (pintype "passive"))
      (node (ref "R6") (pin "1") (pinfunction "1_1") (pintype "passive"))
      (node (ref "TVS2") (pin "4") (pinfunction "IO3_4") (pintype "bidirectional"))
    )
    (net (code "37") (name "/N$13") (class "Default")
      (node (ref "F15") (pin "2") (pinfunction "2_2") (pintype "passive"))
      (node (ref "R64") (pin "1") (pinfunction "1_1") (pintype "passive"))
      (node (ref "TVS9") (pin "4") (pinfunction "IO3_4") (pintype "bidirectional"))
    )
    (net (code "38") (name "/N$14") (class "Default")
      (node (ref "F7") (pin "2") (pinfunction "2_2") (pintype "passive"))
      (node (ref "R7") (pin "1") (pinfunction "1_1") (pintype "passive"))
      (node (ref "TVS2") (pin "6") (pinfunction "IO4_6") (pintype "bidirectional"))
    )
    (net (code "39") (name "/N$15") (class "Default")
      (node (ref "F11") (pin "2") (pinfunction "2_2") (pintype "passive"))
      (node (ref "R60") (pin "1") (pinfunction "1_1") (pintype "passive"))
      (node (ref "TVS6") (pin "4") (pinfunction "IO3_4") (pintype "bidirectional"))
    )
    (net (code "40") (name "/N$16") (class "Default")
      (node (ref "F16") (pin "2") (pinfunction "2_2") (pintype "passive"))
      (node (ref "R65") (pin "1") (pinfunction "1_1") (pintype "passive"))
      (node (ref "TVS9") (pin "6") (pinfunction "IO4_6") (pintype "bidirectional"))
    )
    (net (code "41") (name "/N$17") (class "Default")
      (node (ref "F8") (pin "2") (pinfunction "2_2") (pintype "passive"))
      (node (ref "R8") (pin "1") (pinfunction "1_1") (pintype "passive"))
      (node (ref "TVS2") (pin "1") (pinfunction "IO1_1") (pintype "bidirectional"))
    )
    (net (code "42") (name "/SCL") (class "Default")
      (node (ref "IC5") (pin "15") (pinfunction "PIO0_4/SCL_15") (pintype "bidirectional"))
      (node (ref "JP22") (pin "1") (pinfunction "1_1") (pintype "passive"))
      (node (ref "JP23") (pin "3") (pinfunction "3_3") (pintype "passive"))
      (node (ref "R70") (pin "1") (pinfunction "1_1") (pintype "passive"))
      (node (ref "U3") (pin "1") (pinfunction "SCL_1") (pintype "bidirectional"))
    )
    (net (code "43") (name "/SDA") (class "Default")
      (node (ref "IC5") (pin "16") (pinfunction "PIO0_5/SDA_16") (pintype "bidirectional"))
      (node (ref "JP22") (pin "2") (pinfunction "2_2") (pintype "passive"))
      (node (ref "JP23") (pin "4") (pinfunction "4_4") (pintype "passive"))
      (node (ref "R71") (pin "1") (pinfunction "1_1") (pintype "passive"))
      (node (ref "U3") (pin "3") (pinfunction "SDA_3") (pintype "bidirectional"))
    )
    (net (code "44") (name "/SWD_ISP_EN") (class "Default")
      (node (ref "JP17") (pin "7") (pinfunction "7_7") (pintype "passive"))
      (node (ref "R69") (pin "2") (pinfunction "2_2") (pintype "passive"))
      (node (ref "TVS5") (pin "4") (pinfunction "IO3_4") (pintype "bidirectional"))
    )
    (net (code "45") (name "/SWD_RESET") (class "Default")
      (node (ref "JP17") (pin "10") (pinfunction "10_10") (pintype "passive"))
      (node (ref "R68") (pin "1") (pinfunction "1_1") (pintype "passive"))
      (node (ref "TVS5") (pin "6") (pinfunction "IO4_6") (pintype "bidirectional"))
    )
    (net (code "46") (name "/SWD_SWCLK") (class "Default")
      (node (ref "JP17") (pin "4") (pinfunction "4_4") (pintype "passive"))
      (node (ref "R66") (pin "2") (pinfunction "2_2") (pintype "passive"))
      (node (ref "TVS5") (pin "1") (pinfunction "IO1_1") (pintype "bidirectional"))
    )
    (net (code "47") (name "/SWD_SWDIO") (class "Default")
      (node (ref "JP17") (pin "2") (pinfunction "2_2") (pintype "passive"))
      (node (ref "R67") (pin "2") (pinfunction "2_2") (pintype "passive"))
      (node (ref "TVS5") (pin "3") (pinfunction "IO2_3") (pintype "bidirectional"))
    )
    (net (code "48") (name "/XTALIN") (class "Default")
      (node (ref "C29") (pin "2") (pinfunction "2_2") (pintype "passive"))
      (node (ref "C30") (pin "1") (pinfunction "1_1") (pintype "passive"))
      (node (ref "IC5") (pin "6") (pinfunction "XTALIN_6") (pintype "input"))
    )
    (net (code "49") (name "/XTAL_EN") (class "Default")
      (node (ref "IC5") (pin "1") (pinfunction "PIO2_6/CT32B0_MAT1_1") (pintype "bidirectional"))
    )
    (net (code "50") (name "BUS_V") (class "Default")
      (node (ref "IC5") (pin "42") (pinfunction "PIO1_11/AD7/CT32B1_CAP1_42") (pintype "bidirectional"))
      (node (ref "JP2") (pin "4") (pinfunction "4_4") (pintype "passive"))
    )
    (net (code "51") (name "EIB_IN") (class "Default")
      (node (ref "IC5") (pin "9") (pinfunction "PIO1_8/CT16B1_CAP0_9") (pintype "bidirectional"))
      (node (ref "JP2") (pin "3") (pinfunction "3_3") (pintype "passive"))
    )
    (net (code "52") (name "EIB_OUT") (class "Default")
      (node (ref "IC5") (pin "17") (pinfunction "PIO1_9/CT16B1_MAT0/MOSI1_17") (pintype "bidirectional"))
      (node (ref "JP2") (pin "5") (pinfunction "5_5") (pintype "passive"))
    )
    (net (code "53") (name "GND") (class "Default")
      (node (ref "C1") (pin "1") (pinfunction "1_1") (pintype "passive"))
      (node (ref "C2") (pin "1") (pinfunction "1_1") (pintype "passive"))
      (node (ref "C25") (pin "1") (pinfunction "1_1") (pintype "passive"))
      (node (ref "C26") (pin "1") (pinfunction "1_1") (pintype "passive"))
      (node (ref "C27") (pin "1") (pinfunction "1_1") (pintype "passive"))
      (node (ref "C28") (pin "1") (pinfunction "1_1") (pintype "passive"))
      (node (ref "C29") (pin "1") (pinfunction "1_1") (pintype "passive"))
      (node (ref "C31") (pin "1") (pinfunction "1_1") (pintype "passive"))
      (node (ref "C32") (pin "1") (pinfunction "1_1") (pintype "passive"))
      (node (ref "C33") (pin "1") (pinfunction "1_1") (pintype "passive"))
      (node (ref "C34") (pin "1") (pinfunction "1_1") (pintype "passive"))
      (node (ref "C35") (pin "2") (pinfunction "2_2") (pintype "passive"))
      (node (ref "C36") (pin "2") (pinfunction "2_2") (pintype "passive"))
      (node (ref "D1") (pin "A") (pinfunction "A_A") (pintype "passive"))
      (node (ref "D13") (pin "A") (pinfunction "A_A") (pintype "passive"))
      (node (ref "D14") (pin "A") (pinfunction "A_A") (pintype "passive"))
      (node (ref "D15") (pin "A") (pinfunction "A_A") (pintype "passive"))
      (node (ref "D16") (pin "A") (pinfunction "A_A") (pintype "passive"))
      (node (ref "D17") (pin "A") (pinfunction "A_A") (pintype "passive"))
      (node (ref "D18") (pin "A") (pinfunction "A_A") (pintype "passive"))
      (node (ref "D19") (pin "A") (pinfunction "A_A") (pintype "passive"))
      (node (ref "D2") (pin "A") (pinfunction "A_A") (pintype "passive"))
      (node (ref "D20") (pin "A") (pinfunction "A_A") (pintype "passive"))
      (node (ref "D3") (pin "A") (pinfunction "A_A") (pintype "passive"))
      (node (ref "D4") (pin "A") (pinfunction "A_A") (pintype "passive"))
      (node (ref "D5") (pin "A") (pinfunction "A_A") (pintype "passive"))
      (node (ref "D6") (pin "A") (pinfunction "A_A") (pintype "passive"))
      (node (ref "D7") (pin "A") (pinfunction "A_A") (pintype "passive"))
      (node (ref "D8") (pin "A") (pinfunction "A_A") (pintype "passive"))
      (node (ref "IC5") (pin "41") (pinfunction "VSS(IO)_41") (pintype "power_in"))
      (node (ref "IC5") (pin "5") (pinfunction "VSS_5") (pintype "power_in"))
      (node (ref "IC6") (pin "4") (pinfunction "VSS_4") (pintype "bidirectional"))
      (node (ref "J1") (pin "2") (pinfunction "2_2") (pintype "passive"))
      (node (ref "J3") (pin "1") (pinfunction "1.1_1") (pintype "bidirectional"))
      (node (ref "J3") (pin "2") (pinfunction "1.2_2") (pintype "bidirectional"))
      (node (ref "JP1") (pin "2") (pinfunction "2_2") (pintype "passive"))
      (node (ref "JP17") (pin "9") (pinfunction "9_9") (pintype "passive"))
      (node (ref "JP18") (pin "2") (pinfunction "2_2") (pintype "passive"))
      (node (ref "JP2") (pin "1") (pinfunction "1_1") (pintype "passive"))
      (node (ref "JP22") (pin "4") (pinfunction "4_4") (pintype "passive"))
      (node (ref "JP23") (pin "2") (pinfunction "2_2") (pintype "passive"))
      (node (ref "PRGBTN2") (pin "1") (pinfunction "1_1") (pintype "passive"))
      (node (ref "Q3") (pin "2") (pinfunction "GND_2") (pintype "power_in"))
      (node (ref "TVS1") (pin "2") (pinfunction "GND_2") (pintype "bidirectional"))
      (node (ref "TVS2") (pin "2") (pinfunction "GND_2") (pintype "bidirectional"))
      (node (ref "TVS5") (pin "2") (pinfunction "GND_2") (pintype "bidirectional"))
      (node (ref "TVS6") (pin "2") (pinfunction "GND_2") (pintype "bidirectional"))
      (node (ref "TVS9") (pin "2") (pinfunction "GND_2") (pintype "bidirectional"))
      (node (ref "U3") (pin "2") (pinfunction "GND_2") (pintype "bidirectional"))
      (node (ref "U3") (pin "5") (pinfunction "WP_5") (pintype "bidirectional"))
      (node (ref "X1") (pin "1") (pinfunction "S_1") (pintype "passive"))
    )
    (net (code "54") (name "IO1") (class "Default")
      (node (ref "IC5") (pin "18") (pinfunction "PIO3_4/CT16B0_CAP1/RXD_18") (pintype "bidirectional"))
      (node (ref "R80") (pin "2") (pinfunction "2_2") (pintype "passive"))
    )
    (net (code "55") (name "IO2") (class "Default")
      (node (ref "IC5") (pin "14") (pinfunction "PIO0_3_14") (pintype "bidirectional"))
      (node (ref "R77") (pin "2") (pinfunction "2_2") (pintype "passive"))
    )
    (net (code "56") (name "IO3") (class "Default")
      (node (ref "IC5") (pin "20") (pinfunction "PIO2_5/CT32B0_MAT0_20") (pintype "bidirectional"))
      (node (ref "R78") (pin "2") (pinfunction "2_2") (pintype "passive"))
    )
    (net (code "57") (name "IO4") (class "Default")
      (node (ref "IC5") (pin "23") (pinfunction "PIO0_7/CTS_23") (pintype "bidirectional"))
      (node (ref "R79") (pin "2") (pinfunction "2_2") (pintype "passive"))
    )
    (net (code "58") (name "IO5") (class "Default")
      (node (ref "IC5") (pin "21") (pinfunction "PIO3_5/CT16B1_CAP1/TXD_21") (pintype "bidirectional"))
      (node (ref "R76") (pin "2") (pinfunction "2_2") (pintype "passive"))
    )
    (net (code "59") (name "IO6") (class "Default")
      (node (ref "IC5") (pin "13") (pinfunction "PIO2_1/DSR/SCK1_13") (pintype "bidirectional"))
      (node (ref "R73") (pin "2") (pinfunction "2_2") (pintype "passive"))
    )
    (net (code "60") (name "IO7") (class "Default")
      (node (ref "IC5") (pin "22") (pinfunction "PIO0_6/SCK0_22") (pintype "bidirectional"))
      (node (ref "R74") (pin "2") (pinfunction "2_2") (pintype "passive"))
    )
    (net (code "61") (name "IO8") (class "Default")
      (node (ref "IC5") (pin "24") (pinfunction "PIO2_9/CT32B0_CAP0_24") (pintype "bidirectional"))
      (node (ref "R75") (pin "2") (pinfunction "2_2") (pintype "passive"))
    )
    (net (code "62") (name "IO9") (class "Default")
      (node (ref "IC5") (pin "27") (pinfunction "PIO0_8/MISO0/CT16B0_MAT0_27") (pintype "bidirectional"))
      (node (ref "R12") (pin "2") (pinfunction "2_2") (pintype "passive"))
    )
    (net (code "63") (name "IO10") (class "Default")
      (node (ref "IC5") (pin "25") (pinfunction "PIO2_10_25") (pintype "bidirectional"))
      (node (ref "R9") (pin "2") (pinfunction "2_2") (pintype "passive"))
    )
    (net (code "64") (name "IO11") (class "Default")
      (node (ref "IC5") (pin "30") (pinfunction "PIO1_10/AD6/CT16B1_MAT1/MISO1_30") (pintype "bidirectional"))
      (node (ref "R10") (pin "2") (pinfunction "2_2") (pintype "passive"))
    )
    (net (code "65") (name "IO12") (class "Default")
      (node (ref "IC5") (pin "28") (pinfunction "PIO0_9/MOSI0/CT16B0_MAT1_28") (pintype "bidirectional"))
      (node (ref "R11") (pin "2") (pinfunction "2_2") (pintype "passive"))
    )
    (net (code "66") (name "IO13") (class "Default")
      (node (ref "IC5") (pin "40") (pinfunction "PIO1_4/AD5/CT32B1_MAT3/WAKEUP_40") (pintype "bidirectional"))
      (node (ref "R16") (pin "2") (pinfunction "2_2") (pintype "passive"))
    )
    (net (code "67") (name "IO14") (class "Default")
      (node (ref "IC5") (pin "10") (pinfunction "PIO0_2/SSEL0/CT16B0_CAP0_10") (pintype "bidirectional"))
      (node (ref "R13") (pin "2") (pinfunction "2_2") (pintype "passive"))
    )
    (net (code "68") (name "IO15") (class "Default")
      (node (ref "IC5") (pin "11") (pinfunction "PIO2_7/CT32B0_MAT2/RXD_11") (pintype "bidirectional"))
      (node (ref "R14") (pin "2") (pinfunction "2_2") (pintype "passive"))
    )
    (net (code "69") (name "IO16") (class "Default")
      (node (ref "IC5") (pin "12") (pinfunction "PIO2_8/CT32B0_MAT3/TXD_12") (pintype "bidirectional"))
      (node (ref "R15") (pin "2") (pinfunction "2_2") (pintype "passive"))
    )
    (net (code "70") (name "ISP_EN") (class "Default")
      (node (ref "IC5") (pin "4") (pinfunction "PIO0_1/CLKOUT/CT32B0_MAT2_4") (pintype "bidirectional"))
      (node (ref "R56") (pin "1") (pinfunction "1_1") (pintype "passive"))
      (node (ref "R69") (pin "1") (pinfunction "1_1") (pintype "passive"))
    )
    (net (code "71") (name "MISO1") (class "Default")
      (node (ref "IC5") (pin "26") (pinfunction "PIO2_2/DCD/MISO1_26") (pintype "bidirectional"))
      (node (ref "IC6") (pin "2") (pinfunction "SO_2") (pintype "bidirectional"))
      (node (ref "J1") (pin "4") (pinfunction "4_4") (pintype "passive"))
      (node (ref "JP1") (pin "4") (pinfunction "4_4") (pintype "passive"))
    )
    (net (code "72") (name "MOSI1") (class "Default")
      (node (ref "IC5") (pin "38") (pinfunction "PIO2_3/RI/MOSI1_38") (pintype "bidirectional"))
      (node (ref "IC6") (pin "5") (pinfunction "SI/SDA_5") (pintype "bidirectional"))
      (node (ref "J1") (pin "5") (pinfunction "5_5") (pintype "passive"))
      (node (ref "JP1") (pin "5") (pinfunction "5_5") (pintype "passive"))
    )
    (net (code "73") (name "Net-(D9-A1)") (class "Default")
      (node (ref "D3") (pin "C") (pinfunction "C_C") (pintype "passive"))
      (node (ref "D9") (pin "1") (pinfunction "A1_1") (pintype "passive"))
      (node (ref "R10") (pin "1") (pinfunction "1_1") (pintype "passive"))
      (node (ref "R3") (pin "2") (pinfunction "2_2") (pintype "passive"))
    )
    (net (code "74") (name "Net-(D9-A2)") (class "Default")
      (node (ref "D4") (pin "C") (pinfunction "C_C") (pintype "passive"))
      (node (ref "D9") (pin "2") (pinfunction "A2_2") (pintype "passive"))
      (node (ref "R11") (pin "1") (pinfunction "1_1") (pintype "passive"))
      (node (ref "R4") (pin "2") (pinfunction "2_2") (pintype "passive"))
    )
    (net (code "75") (name "Net-(D10-A1)") (class "Default")
      (node (ref "D10") (pin "1") (pinfunction "A1_1") (pintype "passive"))
      (node (ref "D2") (pin "C") (pinfunction "C_C") (pintype "passive"))
      (node (ref "R2") (pin "2") (pinfunction "2_2") (pintype "passive"))
      (node (ref "R9") (pin "1") (pinfunction "1_1") (pintype "passive"))
    )
    (net (code "76") (name "Net-(D10-A2)") (class "Default")
      (node (ref "D1") (pin "C") (pinfunction "C_C") (pintype "passive"))
      (node (ref "D10") (pin "2") (pinfunction "A2_2") (pintype "passive"))
      (node (ref "R1") (pin "2") (pinfunction "2_2") (pintype "passive"))
      (node (ref "R12") (pin "1") (pinfunction "1_1") (pintype "passive"))
    )
    (net (code "77") (name "Net-(D11-A1)") (class "Default")
      (node (ref "D11") (pin "1") (pinfunction "A1_1") (pintype "passive"))
      (node (ref "D5") (pin "C") (pinfunction "C_C") (pintype "passive"))
      (node (ref "R15") (pin "1") (pinfunction "1_1") (pintype "passive"))
      (node (ref "R8") (pin "2") (pinfunction "2_2") (pintype "passive"))
    )
    (net (code "78") (name "Net-(D11-A2)") (class "Default")
      (node (ref "D11") (pin "2") (pinfunction "A2_2") (pintype "passive"))
      (node (ref "D6") (pin "C") (pinfunction "C_C") (pintype "passive"))
      (node (ref "R14") (pin "1") (pinfunction "1_1") (pintype "passive"))
      (node (ref "R7") (pin "2") (pinfunction "2_2") (pintype "passive"))
    )
    (net (code "79") (name "Net-(D12-A1)") (class "Default")
      (node (ref "D12") (pin "1") (pinfunction "A1_1") (pintype "passive"))
      (node (ref "D8") (pin "C") (pinfunction "C_C") (pintype "passive"))
      (node (ref "R16") (pin "1") (pinfunction "1_1") (pintype "passive"))
      (node (ref "R5") (pin "2") (pinfunction "2_2") (pintype "passive"))
    )
    (net (code "80") (name "Net-(D12-A2)") (class "Default")
      (node (ref "D12") (pin "2") (pinfunction "A2_2") (pintype "passive"))
      (node (ref "D7") (pin "C") (pinfunction "C_C") (pintype "passive"))
      (node (ref "R13") (pin "1") (pinfunction "1_1") (pintype "passive"))
      (node (ref "R6") (pin "2") (pinfunction "2_2") (pintype "passive"))
    )
    (net (code "81") (name "Net-(FB1-P$1)") (class "Default")
      (node (ref "F1") (pin "1") (pinfunction "1_1") (pintype "passive"))
      (node (ref "FB1") (pin "1") (pinfunction "P$1_1") (pintype "passive"))
    )
    (net (code "82") (name "Net-(FB2-P$1)") (class "Default")
      (node (ref "F2") (pin "1") (pinfunction "1_1") (pintype "passive"))
      (node (ref "FB2") (pin "1") (pinfunction "P$1_1") (pintype "passive"))
    )
    (net (code "83") (name "Net-(FB3-P$1)") (class "Default")
      (node (ref "F3") (pin "1") (pinfunction "1_1") (pintype "passive"))
      (node (ref "FB3") (pin "1") (pinfunction "P$1_1") (pintype "passive"))
    )
    (net (code "84") (name "Net-(FB4-P$1)") (class "Default")
      (node (ref "F4") (pin "1") (pinfunction "1_1") (pintype "passive"))
      (node (ref "FB4") (pin "1") (pinfunction "P$1_1") (pintype "passive"))
    )
    (net (code "85") (name "Net-(FB5-P$2)") (class "Default")
      (node (ref "F5") (pin "1") (pinfunction "1_1") (pintype "passive"))
      (node (ref "FB5") (pin "2") (pinfunction "P$2_2") (pintype "passive"))
    )
    (net (code "86") (name "Net-(FB6-P$2)") (class "Default")
      (node (ref "F6") (pin "1") (pinfunction "1_1") (pintype "passive"))
      (node (ref "FB6") (pin "2") (pinfunction "P$2_2") (pintype "passive"))
    )
    (net (code "87") (name "Net-(FB7-P$2)") (class "Default")
      (node (ref "F7") (pin "1") (pinfunction "1_1") (pintype "passive"))
      (node (ref "FB7") (pin "2") (pinfunction "P$2_2") (pintype "passive"))
    )
    (net (code "88") (name "Net-(FB8-P$2)") (class "Default")
      (node (ref "F8") (pin "1") (pinfunction "1_1") (pintype "passive"))
      (node (ref "FB8") (pin "2") (pinfunction "P$2_2") (pintype "passive"))
    )
    (net (code "89") (name "Net-(FB17-P$1)") (class "Default")
      (node (ref "F9") (pin "1") (pinfunction "1_1") (pintype "passive"))
      (node (ref "FB17") (pin "1") (pinfunction "P$1_1") (pintype "passive"))
    )
    (net (code "90") (name "Net-(FB18-P$1)") (class "Default")
      (node (ref "F10") (pin "1") (pinfunction "1_1") (pintype "passive"))
      (node (ref "FB18") (pin "1") (pinfunction "P$1_1") (pintype "passive"))
    )
    (net (code "91") (name "Net-(FB19-P$1)") (class "Default")
      (node (ref "F11") (pin "1") (pinfunction "1_1") (pintype "passive"))
      (node (ref "FB19") (pin "1") (pinfunction "P$1_1") (pintype "passive"))
    )
    (net (code "92") (name "Net-(FB20-P$1)") (class "Default")
      (node (ref "F12") (pin "1") (pinfunction "1_1") (pintype "passive"))
      (node (ref "FB20") (pin "1") (pinfunction "P$1_1") (pintype "passive"))
    )
    (net (code "93") (name "Net-(FB21-P$1)") (class "Default")
      (node (ref "F16") (pin "1") (pinfunction "1_1") (pintype "passive"))
      (node (ref "FB21") (pin "1") (pinfunction "P$1_1") (pintype "passive"))
    )
    (net (code "94") (name "Net-(FB22-P$1)") (class "Default")
      (node (ref "F15") (pin "1") (pinfunction "1_1") (pintype "passive"))
      (node (ref "FB22") (pin "1") (pinfunction "P$1_1") (pintype "passive"))
    )
    (net (code "95") (name "Net-(FB23-P$1)") (class "Default")
      (node (ref "F14") (pin "1") (pinfunction "1_1") (pintype "passive"))
      (node (ref "FB23") (pin "1") (pinfunction "P$1_1") (pintype "passive"))
    )
    (net (code "96") (name "Net-(FB24-P$1)") (class "Default")
      (node (ref "F13") (pin "1") (pinfunction "1_1") (pintype "passive"))
      (node (ref "FB24") (pin "1") (pinfunction "P$1_1") (pintype "passive"))
    )
    (net (code "97") (name "Net-(IC5-PIO1_5{slash}RTS{slash}CT32B0_CAP0)") (class "Default")
      (node (ref "IC5") (pin "45") (pinfunction "PIO1_5/RTS/CT32B0_CAP0_45") (pintype "bidirectional"))
      (node (ref "TP6") (pin "TP") (pinfunction "TP_TP") (pintype "input"))
    )
    (net (code "98") (name "Net-(IC5-PIO2_11{slash}SCK0{slash}CT32B0_CAP1)") (class "Default")
      (node (ref "IC5") (pin "31") (pinfunction "PIO2_11/SCK0/CT32B0_CAP1_31") (pintype "bidirectional"))
      (node (ref "TP1") (pin "TP") (pinfunction "TP_TP") (pintype "input"))
    )
    (net (code "99") (name "Net-(IC5-PIO3_3{slash}RI{slash}CT16B0_CAP0)") (class "Default")
      (node (ref "IC5") (pin "48") (pinfunction "PIO3_3/RI/CT16B0_CAP0_48") (pintype "bidirectional"))
      (node (ref "R81") (pin "1") (pinfunction "1_1") (pintype "passive"))
    )
    (net (code "100") (name "Net-(IC5-TDI{slash}PIO0_11{slash}AD0{slash}CT32B0_MAT3)") (class "Default")
      (node (ref "IC5") (pin "32") (pinfunction "TDI/PIO0_11/AD0/CT32B0_MAT3_32") (pintype "bidirectional"))
      (node (ref "TP2") (pin "TP") (pinfunction "TP_TP") (pintype "input"))
    )
    (net (code "101") (name "Net-(IC5-TDO{slash}PIO1_1{slash}AD2{slash}CT32B1_MAT0)") (class "Default")
      (node (ref "IC5") (pin "34") (pinfunction "TDO/PIO1_1/AD2/CT32B1_MAT0_34") (pintype "bidirectional"))
      (node (ref "TP4") (pin "TP") (pinfunction "TP_TP") (pintype "input"))
    )
    (net (code "102") (name "Net-(IC5-TMS{slash}PIO1_0{slash}AD1{slash}CT32B1_CAP0)") (class "Default")
      (node (ref "IC5") (pin "33") (pinfunction "TMS/PIO1_0/AD1/CT32B1_CAP0_33") (pintype "bidirectional"))
      (node (ref "TP3") (pin "TP") (pinfunction "TP_TP") (pintype "input"))
    )
    (net (code "103") (name "Net-(IC5-TRST{slash}PIO1_2{slash}AD3{slash}CT32B1_MAT1)") (class "Default")
      (node (ref "IC5") (pin "35") (pinfunction "TRST/PIO1_2/AD3/CT32B1_MAT1_35") (pintype "bidirectional"))
      (node (ref "TP5") (pin "TP") (pinfunction "TP_TP") (pintype "input"))
    )
    (net (code "104") (name "Net-(LED5-PadA)") (class "Default")
      (node (ref "LED5") (pin "A") (pinfunction "A_A") (pintype "passive"))
      (node (ref "R57") (pin "1") (pinfunction "1_1") (pintype "passive"))
    )
    (net (code "105") (name "Net-(LED6-PadC)") (class "Default")
      (node (ref "LED6") (pin "C") (pinfunction "C_C") (pintype "passive"))
      (node (ref "R81") (pin "2") (pinfunction "2_2") (pintype "passive"))
    )
    (net (code "106") (name "Net-(Q3-FO)") (class "Default")
      (node (ref "C30") (pin "2") (pinfunction "2_2") (pintype "passive"))
      (node (ref "Q3") (pin "3") (pinfunction "FO_3") (pintype "output"))
    )
    (net (code "107") (name "Net-(TVS1-IO1)") (class "Default")
      (node (ref "F4") (pin "2") (pinfunction "2_2") (pintype "passive"))
      (node (ref "R4") (pin "1") (pinfunction "1_1") (pintype "passive"))
      (node (ref "TVS1") (pin "1") (pinfunction "IO1_1") (pintype "bidirectional"))
    )
    (net (code "108") (name "Net-(TVS1-IO2)") (class "Default")
      (node (ref "F2") (pin "2") (pinfunction "2_2") (pintype "passive"))
      (node (ref "R2") (pin "1") (pinfunction "1_1") (pintype "passive"))
      (node (ref "TVS1") (pin "3") (pinfunction "IO2_3") (pintype "bidirectional"))
    )
    (net (code "109") (name "Net-(TVS1-IO3)") (class "Default")
      (node (ref "F1") (pin "2") (pinfunction "2_2") (pintype "passive"))
      (node (ref "R1") (pin "1") (pinfunction "1_1") (pintype "passive"))
      (node (ref "TVS1") (pin "4") (pinfunction "IO3_4") (pintype "bidirectional"))
    )
    (net (code "110") (name "Net-(TVS1-IO4)") (class "Default")
      (node (ref "F3") (pin "2") (pinfunction "2_2") (pintype "passive"))
      (node (ref "R3") (pin "1") (pinfunction "1_1") (pintype "passive"))
      (node (ref "TVS1") (pin "6") (pinfunction "IO4_6") (pintype "bidirectional"))
    )
    (net (code "111") (name "Net-(TVS1-VBUS)") (class "Default")
      (node (ref "C1") (pin "2") (pinfunction "2_2") (pintype "passive"))
      (node (ref "TVS1") (pin "5") (pinfunction "VBUS_5") (pintype "bidirectional"))
    )
    (net (code "112") (name "Net-(TVS2-VBUS)") (class "Default")
      (node (ref "C2") (pin "2") (pinfunction "2_2") (pintype "passive"))
      (node (ref "TVS2") (pin "5") (pinfunction "VBUS_5") (pintype "bidirectional"))
    )
    (net (code "113") (name "Net-(TVS6-VBUS)") (class "Default")
      (node (ref "C32") (pin "2") (pinfunction "2_2") (pintype "passive"))
      (node (ref "TVS6") (pin "5") (pinfunction "VBUS_5") (pintype "bidirectional"))
    )
    (net (code "114") (name "Net-(TVS9-VBUS)") (class "Default")
      (node (ref "C33") (pin "2") (pinfunction "2_2") (pintype "passive"))
      (node (ref "TVS9") (pin "5") (pinfunction "VBUS_5") (pintype "bidirectional"))
    )
    (net (code "115") (name "PROG") (class "Default")
      (node (ref "IC5") (pin "2") (pinfunction "PIO2_0/DTR/SSEL1_2") (pintype "bidirectional"))
      (node (ref "JP18") (pin "1") (pinfunction "1_1") (pintype "passive"))
      (node (ref "LED5") (pin "C") (pinfunction "C_C") (pintype "passive"))
    )
    (net (code "116") (name "RESET") (class "Default")
      (node (ref "C26") (pin "2") (pinfunction "2_2") (pintype "passive"))
      (node (ref "IC5") (pin "3") (pinfunction "RESET/PIO0_0_3") (pintype "bidirectional"))
      (node (ref "R55") (pin "1") (pinfunction "1_1") (pintype "passive"))
      (node (ref "R68") (pin "2") (pinfunction "2_2") (pintype "passive"))
    )
    (net (code "117") (name "SCK1") (class "Default")
      (node (ref "IC5") (pin "43") (pinfunction "PIO3_2/DCD/CT16B0_MAT2/SCK1_43") (pintype "bidirectional"))
      (node (ref "IC6") (pin "6") (pinfunction "SCK_6") (pintype "bidirectional"))
      (node (ref "J1") (pin "3") (pinfunction "3_3") (pintype "passive"))
      (node (ref "JP1") (pin "3") (pinfunction "3_3") (pintype "passive"))
    )
    (net (code "118") (name "SSEL1") (class "Default")
      (node (ref "IC5") (pin "19") (pinfunction "PIO2_4/CT16B1_MAT1/SSEL1_19") (pintype "bidirectional"))
      (node (ref "IC6") (pin "1") (pinfunction "CS_1") (pintype "bidirectional"))
      (node (ref "J1") (pin "6") (pinfunction "6_6") (pintype "passive"))
      (node (ref "JP1") (pin "6") (pinfunction "6_6") (pintype "passive"))
      (node (ref "R72") (pin "1") (pinfunction "1_1") (pintype "passive"))
    )
    (net (code "119") (name "SWCLK") (class "Default")
      (node (ref "IC5") (pin "29") (pinfunction "SWCLK/PIO0_10/SCK0/CT16B0_MAT2_29") (pintype "bidirectional"))
      (node (ref "R66") (pin "1") (pinfunction "1_1") (pintype "passive"))
    )
    (net (code "120") (name "SWDIO") (class "Default")
      (node (ref "IC5") (pin "39") (pinfunction "SWDIO/PIO1_3/AD4/CT32B1_MAT2_39") (pintype "bidirectional"))
      (node (ref "R67") (pin "1") (pinfunction "1_1") (pintype "passive"))
    )
    (net (code "121") (name "unconnected-(IC5-XTALOUT-Pad7)") (class "Default")
      (node (ref "IC5") (pin "7") (pinfunction "XTALOUT_7") (pintype "output"))
    )
    (net (code "122") (name "unconnected-(JP17-Pad6)") (class "Default")
      (node (ref "JP17") (pin "6") (pinfunction "6_6") (pintype "passive"))
    )
    (net (code "123") (name "unconnected-(JP17-Pad8)") (class "Default")
      (node (ref "JP17") (pin "8") (pinfunction "8_8") (pintype "passive"))
    )
    (net (code "124") (name "unconnected-(JP21-Pad1)") (class "Default")
      (node (ref "JP21") (pin "1") (pinfunction "1_1") (pintype "passive"))
    )
    (net (code "125") (name "unconnected-(JP21-Pad2)") (class "Default")
      (node (ref "JP21") (pin "2") (pinfunction "2_2") (pintype "passive"))
    )
  )
)
